# Keypads.net
KiCad netlist of a schematic drawn in EAGLE
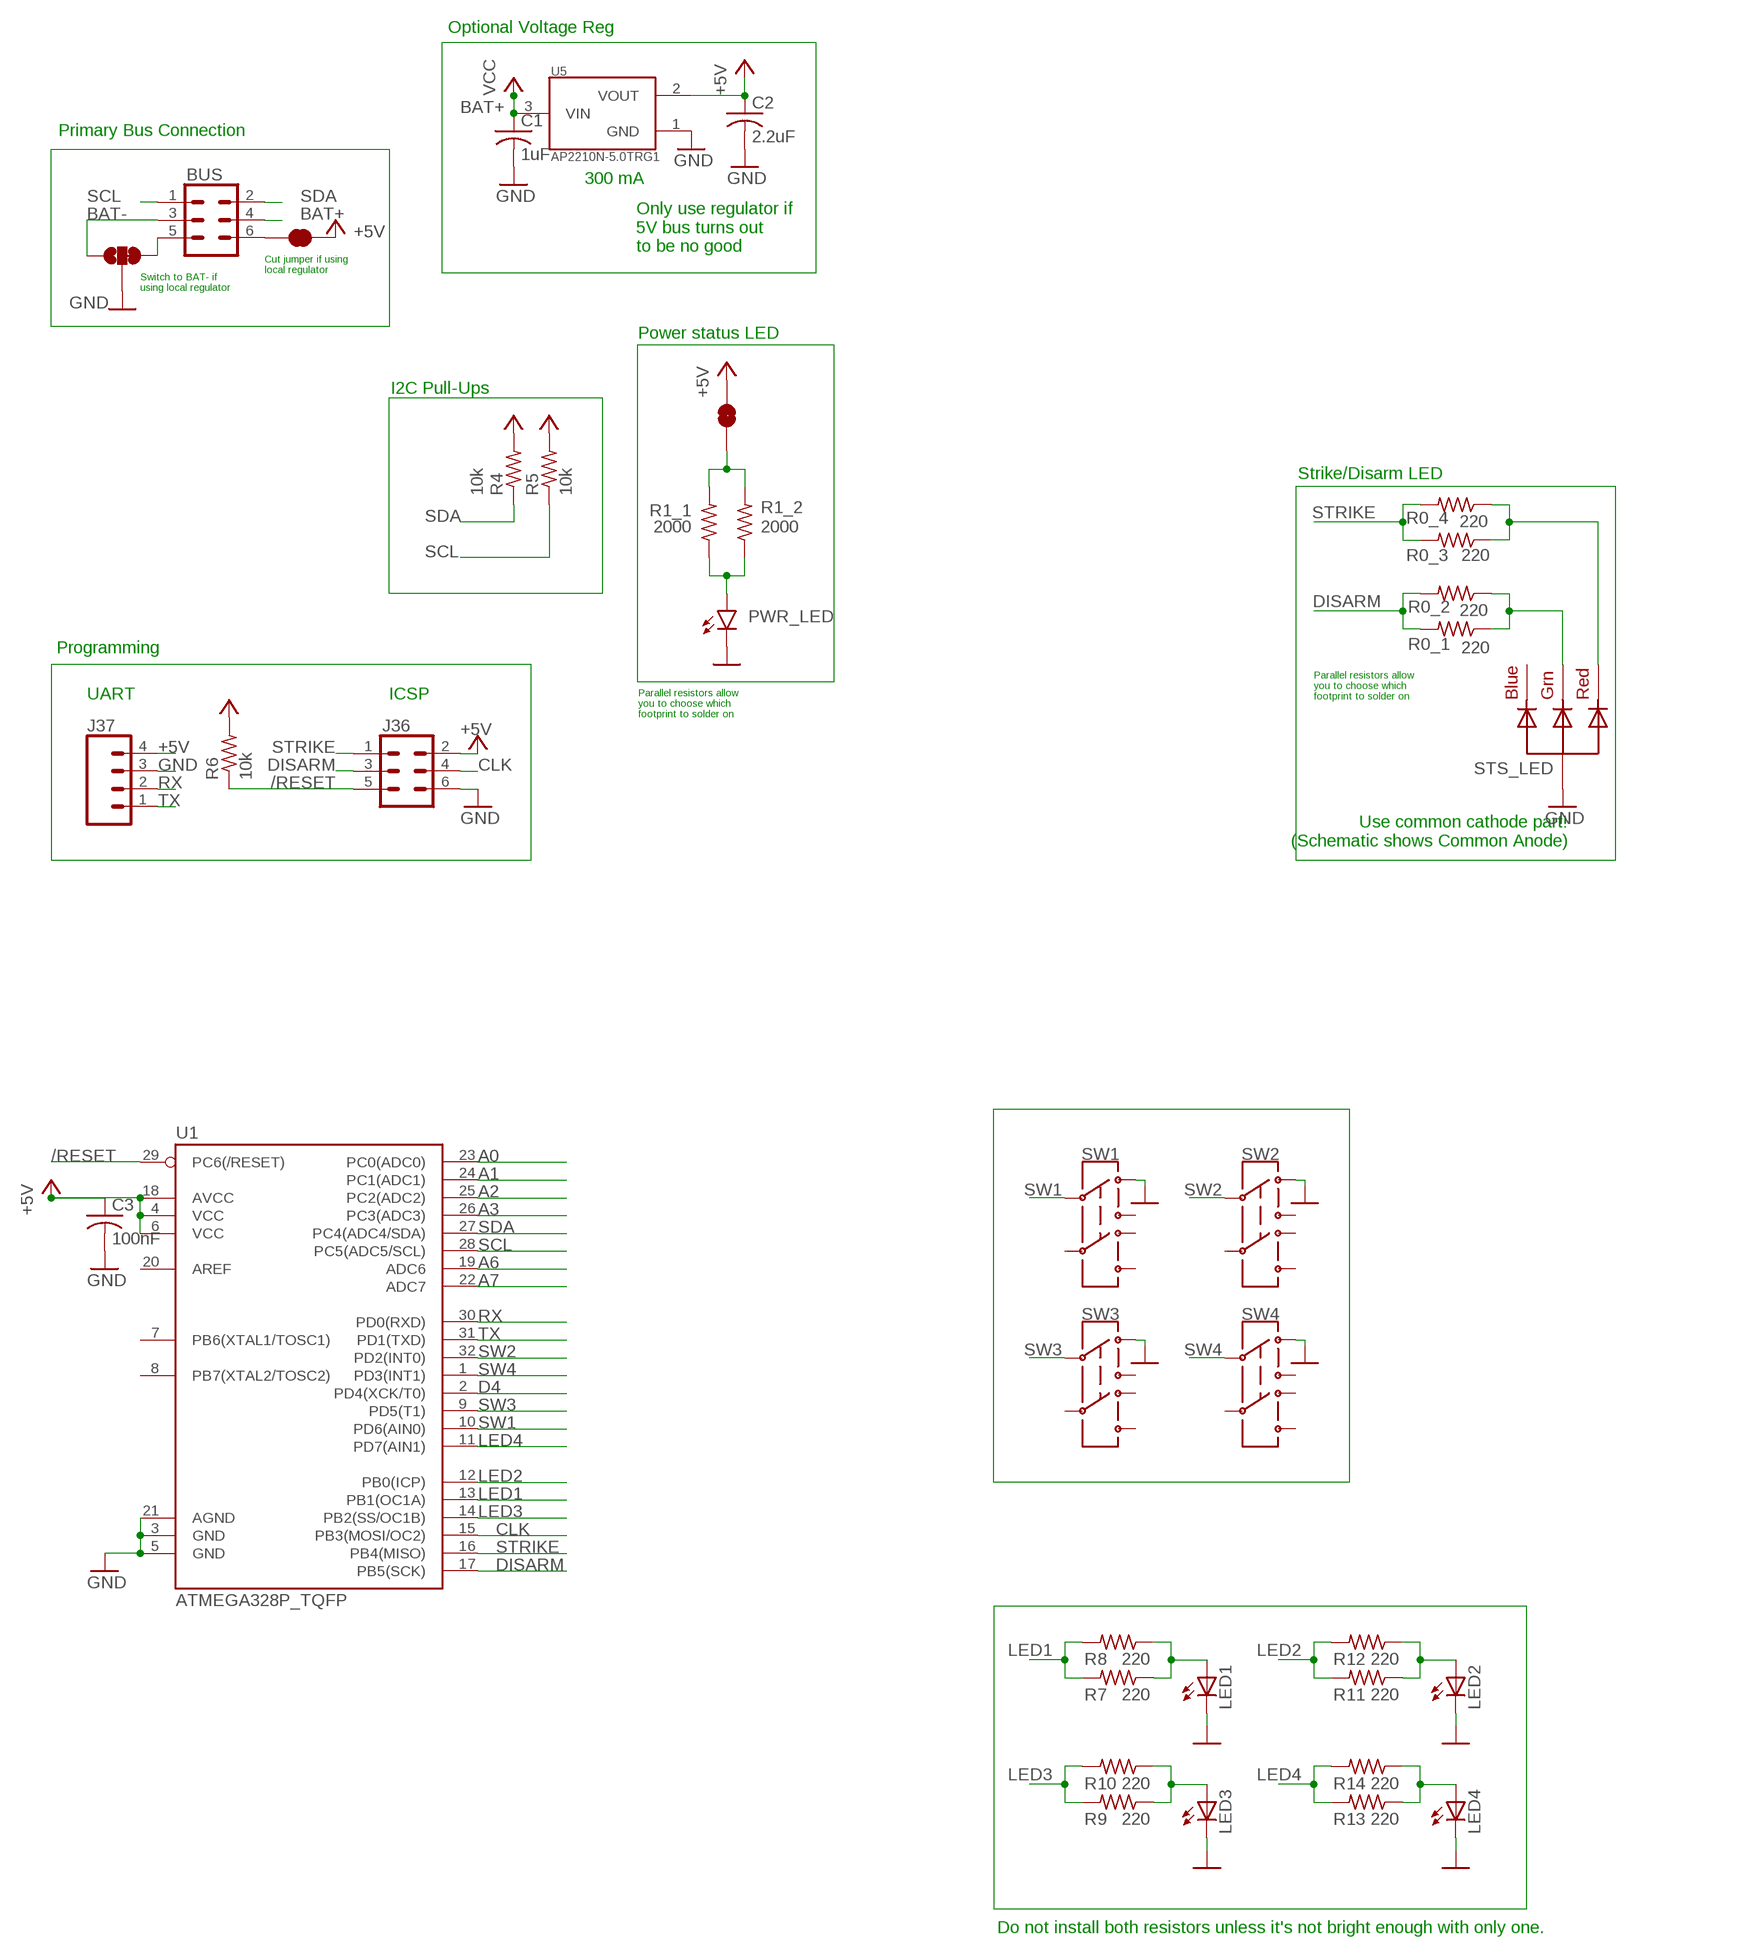
[diagram p0: schematic, sheet 1]

(export (version "E")
  (design (tool "Eeschema 10.0.6"))
  (components
    (comp (ref "BUS")
      (value "CONN_03X2SHROUD")
      (footprint "eagle-import:2X3-SHROUDED")
      (libsource (lib "eagle-import") (part "CONN_03X2SHROUD"))
    )
    (comp (ref "C1")
      (value "1uF")
      (footprint "eagle-import:C0805")
      (libsource (lib "eagle-import") (part "C-USC0805"))
    )
    (comp (ref "C2")
      (value "2.2uF")
      (footprint "eagle-import:C0805")
      (libsource (lib "eagle-import") (part "C-USC0805"))
    )
    (comp (ref "C3")
      (value "100nF")
      (footprint "eagle-import:C0805")
      (libsource (lib "eagle-import") (part "C-USC0805"))
    )
    (comp (ref "J36")
      (value "CONN_03X22X3_SILK_MALE_PTH")
      (footprint "eagle-import:2X3")
      (libsource (lib "eagle-import") (part "CONN_03X22X3_SILK_MALE_PTH"))
    )
    (comp (ref "J37")
      (value "CONN_04")
      (footprint "eagle-import:1X04")
      (libsource (lib "eagle-import") (part "CONN_04"))
    )
    (comp (ref "JP1")
      (value "JUMPER-SMT_2_NC_TRACE_SILK")
      (footprint "eagle-import:SMT-JUMPER_2_NC_TRACE_SILK")
      (libsource (lib "eagle-import") (part "JUMPER-SMT_2_NC_TRACE_SILK"))
    )
    (comp (ref "JP2")
      (value "JUMPER-SMT_3_1-NC_TRACE_SILK")
      (footprint "eagle-import:SMT-JUMPER_3_1-NC_TRACE_SILK")
      (libsource (lib "eagle-import") (part "JUMPER-SMT_3_1-NC_TRACE_SILK"))
    )
    (comp (ref "JP3")
      (value "JUMPER-SMT_2_NC_TRACE_SILK")
      (footprint "eagle-import:SMT-JUMPER_2_NC_TRACE_SILK")
      (libsource (lib "eagle-import") (part "JUMPER-SMT_2_NC_TRACE_SILK"))
    )
    (comp (ref "LED1")
      (value "LEDCHIP-LED0603")
      (footprint "eagle-import:CHIP-LED0603")
      (libsource (lib "eagle-import") (part "LEDCHIP-LED0603"))
    )
    (comp (ref "LED2")
      (value "LEDCHIP-LED0603")
      (footprint "eagle-import:CHIP-LED0603")
      (libsource (lib "eagle-import") (part "LEDCHIP-LED0603"))
    )
    (comp (ref "LED3")
      (value "LEDCHIP-LED0603")
      (footprint "eagle-import:CHIP-LED0603")
      (libsource (lib "eagle-import") (part "LEDCHIP-LED0603"))
    )
    (comp (ref "LED4")
      (value "LEDCHIP-LED0603")
      (footprint "eagle-import:CHIP-LED0603")
      (libsource (lib "eagle-import") (part "LEDCHIP-LED0603"))
    )
    (comp (ref "PWR_LED")
      (value "LED3MM")
      (footprint "eagle-import:LED_3MM")
      (libsource (lib "eagle-import") (part "LED3MM"))
    )
    (comp (ref "R0_1")
      (value "220")
      (footprint "eagle-import:0204_7")
      (libsource (lib "eagle-import") (part "R-US_0204/7"))
    )
    (comp (ref "R0_2")
      (value "220")
      (footprint "eagle-import:R0805")
      (libsource (lib "eagle-import") (part "R-US_R0805"))
    )
    (comp (ref "R0_3")
      (value "220")
      (footprint "eagle-import:0204_7")
      (libsource (lib "eagle-import") (part "R-US_0204/7"))
    )
    (comp (ref "R0_4")
      (value "220")
      (footprint "eagle-import:R0805")
      (libsource (lib "eagle-import") (part "R-US_R0805"))
    )
    (comp (ref "R1_1")
      (value "2000")
      (footprint "eagle-import:0204_7")
      (libsource (lib "eagle-import") (part "R-US_0204/7"))
    )
    (comp (ref "R1_2")
      (value "2000")
      (footprint "eagle-import:R0805")
      (libsource (lib "eagle-import") (part "R-US_R0805"))
    )
    (comp (ref "R4")
      (value "10k")
      (footprint "eagle-import:0204_7")
      (libsource (lib "eagle-import") (part "R-US_0204/7"))
    )
    (comp (ref "R5")
      (value "10k")
      (footprint "eagle-import:0204_7")
      (libsource (lib "eagle-import") (part "R-US_0204/7"))
    )
    (comp (ref "R6")
      (value "10k")
      (footprint "eagle-import:0204_7")
      (libsource (lib "eagle-import") (part "R-US_0204/7"))
    )
    (comp (ref "R7")
      (value "220")
      (footprint "eagle-import:R0805")
      (libsource (lib "eagle-import") (part "R-US_R0805"))
    )
    (comp (ref "R8")
      (value "220")
      (footprint "eagle-import:R0805")
      (libsource (lib "eagle-import") (part "R-US_R0805"))
    )
    (comp (ref "R9")
      (value "220")
      (footprint "eagle-import:R0805")
      (libsource (lib "eagle-import") (part "R-US_R0805"))
    )
    (comp (ref "R10")
      (value "220")
      (footprint "eagle-import:R0805")
      (libsource (lib "eagle-import") (part "R-US_R0805"))
    )
    (comp (ref "R11")
      (value "220")
      (footprint "eagle-import:R0805")
      (libsource (lib "eagle-import") (part "R-US_R0805"))
    )
    (comp (ref "R12")
      (value "220")
      (footprint "eagle-import:R0805")
      (libsource (lib "eagle-import") (part "R-US_R0805"))
    )
    (comp (ref "R13")
      (value "220")
      (footprint "eagle-import:R0805")
      (libsource (lib "eagle-import") (part "R-US_R0805"))
    )
    (comp (ref "R14")
      (value "220")
      (footprint "eagle-import:R0805")
      (libsource (lib "eagle-import") (part "R-US_R0805"))
    )
    (comp (ref "STS_LED")
      (value "RGBLED_CA-5MM")
      (footprint "eagle-import:LED5MMRGB")
      (libsource (lib "eagle-import") (part "RGBLED_CA-5MM"))
    )
    (comp (ref "SW1")
      (value "MHPS2283N-SWITCH-PUSH-DPDT")
      (footprint "eagle-import:MHPS2283N")
      (libsource (lib "eagle-import") (part "MHPS2283N-SWITCH-PUSH-DPDT"))
    )
    (comp (ref "SW2")
      (value "MHPS2283N-SWITCH-PUSH-DPDT")
      (footprint "eagle-import:MHPS2283N")
      (libsource (lib "eagle-import") (part "MHPS2283N-SWITCH-PUSH-DPDT"))
    )
    (comp (ref "SW3")
      (value "MHPS2283N-SWITCH-PUSH-DPDT")
      (footprint "eagle-import:MHPS2283N")
      (libsource (lib "eagle-import") (part "MHPS2283N-SWITCH-PUSH-DPDT"))
    )
    (comp (ref "SW4")
      (value "MHPS2283N-SWITCH-PUSH-DPDT")
      (footprint "eagle-import:MHPS2283N")
      (libsource (lib "eagle-import") (part "MHPS2283N-SWITCH-PUSH-DPDT"))
    )
    (comp (ref "U1")
      (value "ATMEGA328P_TQFP")
      (footprint "eagle-import:TQFP32-08")
      (libsource (lib "eagle-import") (part "ATMEGA328P_TQFP"))
    )
    (comp (ref "U5")
      (value "AP2210N-5.0TRG1")
      (footprint "eagle-import:SOT95P280X145-3N")
      (fields
        (field (name "DIGI-KEY_PART_NUMBER") "AP2210N-5.0TRG1DICT-ND")
        (field (name "MF") "Diodes Inc.")
      )
      (libsource (lib "eagle-import") (part "AP2210N-5.0TRG1"))
    )
  )
  (nets
    (net (code "1") (name "+5V") (class "Default")
      (node (ref "C2") (pin "1") (pinfunction "1_1") (pintype "passive"))
      (node (ref "C3") (pin "1") (pinfunction "1_1") (pintype "passive"))
      (node (ref "J36") (pin "2") (pinfunction "2_2") (pintype "bidirectional"))
      (node (ref "J37") (pin "4") (pinfunction "4_4") (pintype "passive"))
      (node (ref "JP1") (pin "2") (pinfunction "2_2") (pintype "passive"))
      (node (ref "JP3") (pin "2") (pinfunction "2_2") (pintype "passive"))
      (node (ref "R4") (pin "2") (pinfunction "2_2") (pintype "passive"))
      (node (ref "R5") (pin "2") (pinfunction "2_2") (pintype "passive"))
      (node (ref "R6") (pin "2") (pinfunction "2_2") (pintype "passive"))
      (node (ref "U1") (pin "18") (pinfunction "AVCC_18") (pintype "bidirectional"))
      (node (ref "U1") (pin "4") (pinfunction "VCC_4") (pintype "bidirectional"))
      (node (ref "U1") (pin "6") (pinfunction "VCC_6") (pintype "bidirectional"))
      (node (ref "U5") (pin "2") (pinfunction "VOUT_2") (pintype "output"))
    )
    (net (code "2") (name "/A0") (class "Default")
      (node (ref "U1") (pin "23") (pinfunction "PC0(ADC0)_23") (pintype "bidirectional"))
    )
    (net (code "3") (name "/A1") (class "Default")
      (node (ref "U1") (pin "24") (pinfunction "PC1(ADC1)_24") (pintype "bidirectional"))
    )
    (net (code "4") (name "/A2") (class "Default")
      (node (ref "U1") (pin "25") (pinfunction "PC2(ADC2)_25") (pintype "bidirectional"))
    )
    (net (code "5") (name "/A3") (class "Default")
      (node (ref "U1") (pin "26") (pinfunction "PC3(ADC3)_26") (pintype "bidirectional"))
    )
    (net (code "6") (name "/A6") (class "Default")
      (node (ref "U1") (pin "19") (pinfunction "ADC6_19") (pintype "bidirectional"))
    )
    (net (code "7") (name "/A7") (class "Default")
      (node (ref "U1") (pin "22") (pinfunction "ADC7_22") (pintype "bidirectional"))
    )
    (net (code "8") (name "/BAT-") (class "Default")
      (node (ref "BUS") (pin "3") (pinfunction "3_3") (pintype "bidirectional"))
      (node (ref "JP2") (pin "1") (pinfunction "1_1") (pintype "passive"))
    )
    (net (code "9") (name "/CLK") (class "Default")
      (node (ref "J36") (pin "4") (pinfunction "4_4") (pintype "bidirectional"))
      (node (ref "U1") (pin "15") (pinfunction "PB3(MOSI/OC2)_15") (pintype "bidirectional"))
    )
    (net (code "10") (name "/D4") (class "Default")
      (node (ref "U1") (pin "2") (pinfunction "PD4(XCK/T0)_2") (pintype "bidirectional"))
    )
    (net (code "11") (name "/DISARM") (class "Default")
      (node (ref "J36") (pin "3") (pinfunction "3_3") (pintype "bidirectional"))
      (node (ref "R0_1") (pin "2") (pinfunction "2_2") (pintype "passive"))
      (node (ref "R0_2") (pin "2") (pinfunction "2_2") (pintype "passive"))
      (node (ref "U1") (pin "17") (pinfunction "PB5(SCK)_17") (pintype "bidirectional"))
    )
    (net (code "12") (name "/LED1") (class "Default")
      (node (ref "R7") (pin "2") (pinfunction "2_2") (pintype "passive"))
      (node (ref "R8") (pin "2") (pinfunction "2_2") (pintype "passive"))
      (node (ref "U1") (pin "13") (pinfunction "PB1(OC1A)_13") (pintype "bidirectional"))
    )
    (net (code "13") (name "/LED2") (class "Default")
      (node (ref "R11") (pin "2") (pinfunction "2_2") (pintype "passive"))
      (node (ref "R12") (pin "2") (pinfunction "2_2") (pintype "passive"))
      (node (ref "U1") (pin "12") (pinfunction "PB0(ICP)_12") (pintype "bidirectional"))
    )
    (net (code "14") (name "/LED3") (class "Default")
      (node (ref "R10") (pin "2") (pinfunction "2_2") (pintype "passive"))
      (node (ref "R9") (pin "2") (pinfunction "2_2") (pintype "passive"))
      (node (ref "U1") (pin "14") (pinfunction "PB2(SS/OC1B)_14") (pintype "bidirectional"))
    )
    (net (code "15") (name "/LED4") (class "Default")
      (node (ref "R13") (pin "2") (pinfunction "2_2") (pintype "passive"))
      (node (ref "R14") (pin "2") (pinfunction "2_2") (pintype "passive"))
      (node (ref "U1") (pin "11") (pinfunction "PD7(AIN1)_11") (pintype "bidirectional"))
    )
    (net (code "16") (name "/RX") (class "Default")
      (node (ref "J37") (pin "2") (pinfunction "2_2") (pintype "passive"))
      (node (ref "U1") (pin "30") (pinfunction "PD0(RXD)_30") (pintype "bidirectional"))
    )
    (net (code "17") (name "/SCL") (class "Default")
      (node (ref "BUS") (pin "1") (pinfunction "1_1") (pintype "bidirectional"))
      (node (ref "R5") (pin "1") (pinfunction "1_1") (pintype "passive"))
      (node (ref "U1") (pin "28") (pinfunction "PC5(ADC5/SCL)_28") (pintype "bidirectional"))
    )
    (net (code "18") (name "/SDA") (class "Default")
      (node (ref "BUS") (pin "2") (pinfunction "2_2") (pintype "bidirectional"))
      (node (ref "R4") (pin "1") (pinfunction "1_1") (pintype "passive"))
      (node (ref "U1") (pin "27") (pinfunction "PC4(ADC4/SDA)_27") (pintype "bidirectional"))
    )
    (net (code "19") (name "/STRIKE") (class "Default")
      (node (ref "J36") (pin "1") (pinfunction "1_1") (pintype "bidirectional"))
      (node (ref "R0_3") (pin "2") (pinfunction "2_2") (pintype "passive"))
      (node (ref "R0_4") (pin "2") (pinfunction "2_2") (pintype "passive"))
      (node (ref "U1") (pin "16") (pinfunction "PB4(MISO)_16") (pintype "bidirectional"))
    )
    (net (code "20") (name "/SW1") (class "Default")
      (node (ref "SW1") (pin "P$2") (pinfunction "2_P$2") (pintype "bidirectional"))
      (node (ref "U1") (pin "10") (pinfunction "PD6(AIN0)_10") (pintype "bidirectional"))
    )
    (net (code "21") (name "/SW2") (class "Default")
      (node (ref "SW2") (pin "P$2") (pinfunction "2_P$2") (pintype "bidirectional"))
      (node (ref "U1") (pin "32") (pinfunction "PD2(INT0)_32") (pintype "bidirectional"))
    )
    (net (code "22") (name "/SW3") (class "Default")
      (node (ref "SW3") (pin "P$2") (pinfunction "2_P$2") (pintype "bidirectional"))
      (node (ref "U1") (pin "9") (pinfunction "PD5(T1)_9") (pintype "bidirectional"))
    )
    (net (code "23") (name "/SW4") (class "Default")
      (node (ref "SW4") (pin "P$2") (pinfunction "2_P$2") (pintype "bidirectional"))
      (node (ref "U1") (pin "1") (pinfunction "PD3(INT1)_1") (pintype "bidirectional"))
    )
    (net (code "24") (name "/TX") (class "Default")
      (node (ref "J37") (pin "1") (pinfunction "1_1") (pintype "passive"))
      (node (ref "U1") (pin "31") (pinfunction "PD1(TXD)_31") (pintype "bidirectional"))
    )
    (net (code "25") (name "/{slash}RESET") (class "Default")
      (node (ref "J36") (pin "5") (pinfunction "5_5") (pintype "bidirectional"))
      (node (ref "R6") (pin "1") (pinfunction "1_1") (pintype "passive"))
      (node (ref "U1") (pin "29") (pinfunction "PC6(/RESET)_29") (pintype "bidirectional"))
    )
    (net (code "26") (name "GND") (class "Default")
      (node (ref "C1") (pin "2") (pinfunction "2_2") (pintype "passive"))
      (node (ref "C2") (pin "2") (pinfunction "2_2") (pintype "passive"))
      (node (ref "C3") (pin "2") (pinfunction "2_2") (pintype "passive"))
      (node (ref "J36") (pin "6") (pinfunction "6_6") (pintype "bidirectional"))
      (node (ref "J37") (pin "3") (pinfunction "3_3") (pintype "passive"))
      (node (ref "JP2") (pin "2") (pinfunction "2_2") (pintype "passive"))
      (node (ref "LED1") (pin "C") (pinfunction "C_C") (pintype "passive"))
      (node (ref "LED2") (pin "C") (pinfunction "C_C") (pintype "passive"))
      (node (ref "LED3") (pin "C") (pinfunction "C_C") (pintype "passive"))
      (node (ref "LED4") (pin "C") (pinfunction "C_C") (pintype "passive"))
      (node (ref "PWR_LED") (pin "K") (pinfunction "C_K") (pintype "passive"))
      (node (ref "STS_LED") (pin "2") (pinfunction "VCC_2") (pintype "bidirectional"))
      (node (ref "SW1") (pin "P$1") (pinfunction "1_P$1") (pintype "bidirectional"))
      (node (ref "SW2") (pin "P$1") (pinfunction "1_P$1") (pintype "bidirectional"))
      (node (ref "SW3") (pin "P$1") (pinfunction "1_P$1") (pintype "bidirectional"))
      (node (ref "SW4") (pin "P$1") (pinfunction "1_P$1") (pintype "bidirectional"))
      (node (ref "U1") (pin "21") (pinfunction "AGND_21") (pintype "bidirectional"))
      (node (ref "U1") (pin "3") (pinfunction "GND_3") (pintype "bidirectional"))
      (node (ref "U1") (pin "5") (pinfunction "GND_5") (pintype "bidirectional"))
      (node (ref "U5") (pin "1") (pinfunction "GND_1") (pintype "power_in"))
    )
    (net (code "27") (name "Net-(BUS-Pad5)") (class "Default")
      (node (ref "BUS") (pin "5") (pinfunction "5_5") (pintype "bidirectional"))
      (node (ref "JP2") (pin "3") (pinfunction "3_3") (pintype "passive"))
    )
    (net (code "28") (name "Net-(BUS-Pad6)") (class "Default")
      (node (ref "BUS") (pin "6") (pinfunction "6_6") (pintype "bidirectional"))
      (node (ref "JP1") (pin "1") (pinfunction "1_1") (pintype "passive"))
    )
    (net (code "29") (name "Net-(JP3-Pad1)") (class "Default")
      (node (ref "JP3") (pin "1") (pinfunction "1_1") (pintype "passive"))
      (node (ref "R1_1") (pin "2") (pinfunction "2_2") (pintype "passive"))
      (node (ref "R1_2") (pin "2") (pinfunction "2_2") (pintype "passive"))
    )
    (net (code "30") (name "Net-(LED1-PadA)") (class "Default")
      (node (ref "LED1") (pin "A") (pinfunction "A_A") (pintype "passive"))
      (node (ref "R7") (pin "1") (pinfunction "1_1") (pintype "passive"))
      (node (ref "R8") (pin "1") (pinfunction "1_1") (pintype "passive"))
    )
    (net (code "31") (name "Net-(LED2-PadA)") (class "Default")
      (node (ref "LED2") (pin "A") (pinfunction "A_A") (pintype "passive"))
      (node (ref "R11") (pin "1") (pinfunction "1_1") (pintype "passive"))
      (node (ref "R12") (pin "1") (pinfunction "1_1") (pintype "passive"))
    )
    (net (code "32") (name "Net-(LED3-PadA)") (class "Default")
      (node (ref "LED3") (pin "A") (pinfunction "A_A") (pintype "passive"))
      (node (ref "R10") (pin "1") (pinfunction "1_1") (pintype "passive"))
      (node (ref "R9") (pin "1") (pinfunction "1_1") (pintype "passive"))
    )
    (net (code "33") (name "Net-(LED4-PadA)") (class "Default")
      (node (ref "LED4") (pin "A") (pinfunction "A_A") (pintype "passive"))
      (node (ref "R13") (pin "1") (pinfunction "1_1") (pintype "passive"))
      (node (ref "R14") (pin "1") (pinfunction "1_1") (pintype "passive"))
    )
    (net (code "34") (name "Net-(PWR_LED-PadA)") (class "Default")
      (node (ref "PWR_LED") (pin "A") (pinfunction "A_A") (pintype "passive"))
      (node (ref "R1_1") (pin "1") (pinfunction "1_1") (pintype "passive"))
      (node (ref "R1_2") (pin "1") (pinfunction "1_1") (pintype "passive"))
    )
    (net (code "35") (name "Net-(STS_LED-GREEN)") (class "Default")
      (node (ref "R0_1") (pin "1") (pinfunction "1_1") (pintype "passive"))
      (node (ref "R0_2") (pin "1") (pinfunction "1_1") (pintype "passive"))
      (node (ref "STS_LED") (pin "3") (pinfunction "GREEN_3") (pintype "bidirectional"))
    )
    (net (code "36") (name "Net-(STS_LED-RED)") (class "Default")
      (node (ref "R0_3") (pin "1") (pinfunction "1_1") (pintype "passive"))
      (node (ref "R0_4") (pin "1") (pinfunction "1_1") (pintype "passive"))
      (node (ref "STS_LED") (pin "1") (pinfunction "RED_1") (pintype "bidirectional"))
    )
    (net (code "37") (name "VCC") (class "Default")
      (node (ref "BUS") (pin "4") (pinfunction "4_4") (pintype "bidirectional"))
      (node (ref "C1") (pin "1") (pinfunction "1_1") (pintype "passive"))
      (node (ref "U5") (pin "3") (pinfunction "VIN_3") (pintype "input"))
    )
    (net (code "38") (name "unconnected-(STS_LED-BLUE-Pad4)") (class "Default")
      (node (ref "STS_LED") (pin "4") (pinfunction "BLUE_4") (pintype "bidirectional"))
    )
    (net (code "39") (name "unconnected-(SW1-3-PadP$3)") (class "Default")
      (node (ref "SW1") (pin "P$3") (pinfunction "3_P$3") (pintype "bidirectional"))
    )
    (net (code "40") (name "unconnected-(SW1-4-PadP$6)") (class "Default")
      (node (ref "SW1") (pin "P$6") (pinfunction "4_P$6") (pintype "bidirectional"))
    )
    (net (code "41") (name "unconnected-(SW1-5-PadP$5)") (class "Default")
      (node (ref "SW1") (pin "P$5") (pinfunction "5_P$5") (pintype "bidirectional"))
    )
    (net (code "42") (name "unconnected-(SW1-6-PadP$4)") (class "Default")
      (node (ref "SW1") (pin "P$4") (pinfunction "6_P$4") (pintype "bidirectional"))
    )
    (net (code "43") (name "unconnected-(SW2-3-PadP$3)") (class "Default")
      (node (ref "SW2") (pin "P$3") (pinfunction "3_P$3") (pintype "bidirectional"))
    )
    (net (code "44") (name "unconnected-(SW2-4-PadP$6)") (class "Default")
      (node (ref "SW2") (pin "P$6") (pinfunction "4_P$6") (pintype "bidirectional"))
    )
    (net (code "45") (name "unconnected-(SW2-5-PadP$5)") (class "Default")
      (node (ref "SW2") (pin "P$5") (pinfunction "5_P$5") (pintype "bidirectional"))
    )
    (net (code "46") (name "unconnected-(SW2-6-PadP$4)") (class "Default")
      (node (ref "SW2") (pin "P$4") (pinfunction "6_P$4") (pintype "bidirectional"))
    )
    (net (code "47") (name "unconnected-(SW3-3-PadP$3)") (class "Default")
      (node (ref "SW3") (pin "P$3") (pinfunction "3_P$3") (pintype "bidirectional"))
    )
    (net (code "48") (name "unconnected-(SW3-4-PadP$6)") (class "Default")
      (node (ref "SW3") (pin "P$6") (pinfunction "4_P$6") (pintype "bidirectional"))
    )
    (net (code "49") (name "unconnected-(SW3-5-PadP$5)") (class "Default")
      (node (ref "SW3") (pin "P$5") (pinfunction "5_P$5") (pintype "bidirectional"))
    )
    (net (code "50") (name "unconnected-(SW3-6-PadP$4)") (class "Default")
      (node (ref "SW3") (pin "P$4") (pinfunction "6_P$4") (pintype "bidirectional"))
    )
    (net (code "51") (name "unconnected-(SW4-3-PadP$3)") (class "Default")
      (node (ref "SW4") (pin "P$3") (pinfunction "3_P$3") (pintype "bidirectional"))
    )
    (net (code "52") (name "unconnected-(SW4-4-PadP$6)") (class "Default")
      (node (ref "SW4") (pin "P$6") (pinfunction "4_P$6") (pintype "bidirectional"))
    )
    (net (code "53") (name "unconnected-(SW4-5-PadP$5)") (class "Default")
      (node (ref "SW4") (pin "P$5") (pinfunction "5_P$5") (pintype "bidirectional"))
    )
    (net (code "54") (name "unconnected-(SW4-6-PadP$4)") (class "Default")
      (node (ref "SW4") (pin "P$4") (pinfunction "6_P$4") (pintype "bidirectional"))
    )
    (net (code "55") (name "unconnected-(U1-AREF-Pad20)") (class "Default")
      (node (ref "U1") (pin "20") (pinfunction "AREF_20") (pintype "bidirectional"))
    )
    (net (code "56") (name "unconnected-(U1-PB6(XTAL1{slash}TOSC1)-Pad7)") (class "Default")
      (node (ref "U1") (pin "7") (pinfunction "PB6(XTAL1/TOSC1)_7") (pintype "bidirectional"))
    )
    (net (code "57") (name "unconnected-(U1-PB7(XTAL2{slash}TOSC2)-Pad8)") (class "Default")
      (node (ref "U1") (pin "8") (pinfunction "PB7(XTAL2/TOSC2)_8") (pintype "bidirectional"))
    )
  )
)
